# lazurite_rev3_2.net
KiCad netlist of a schematic drawn in EAGLE
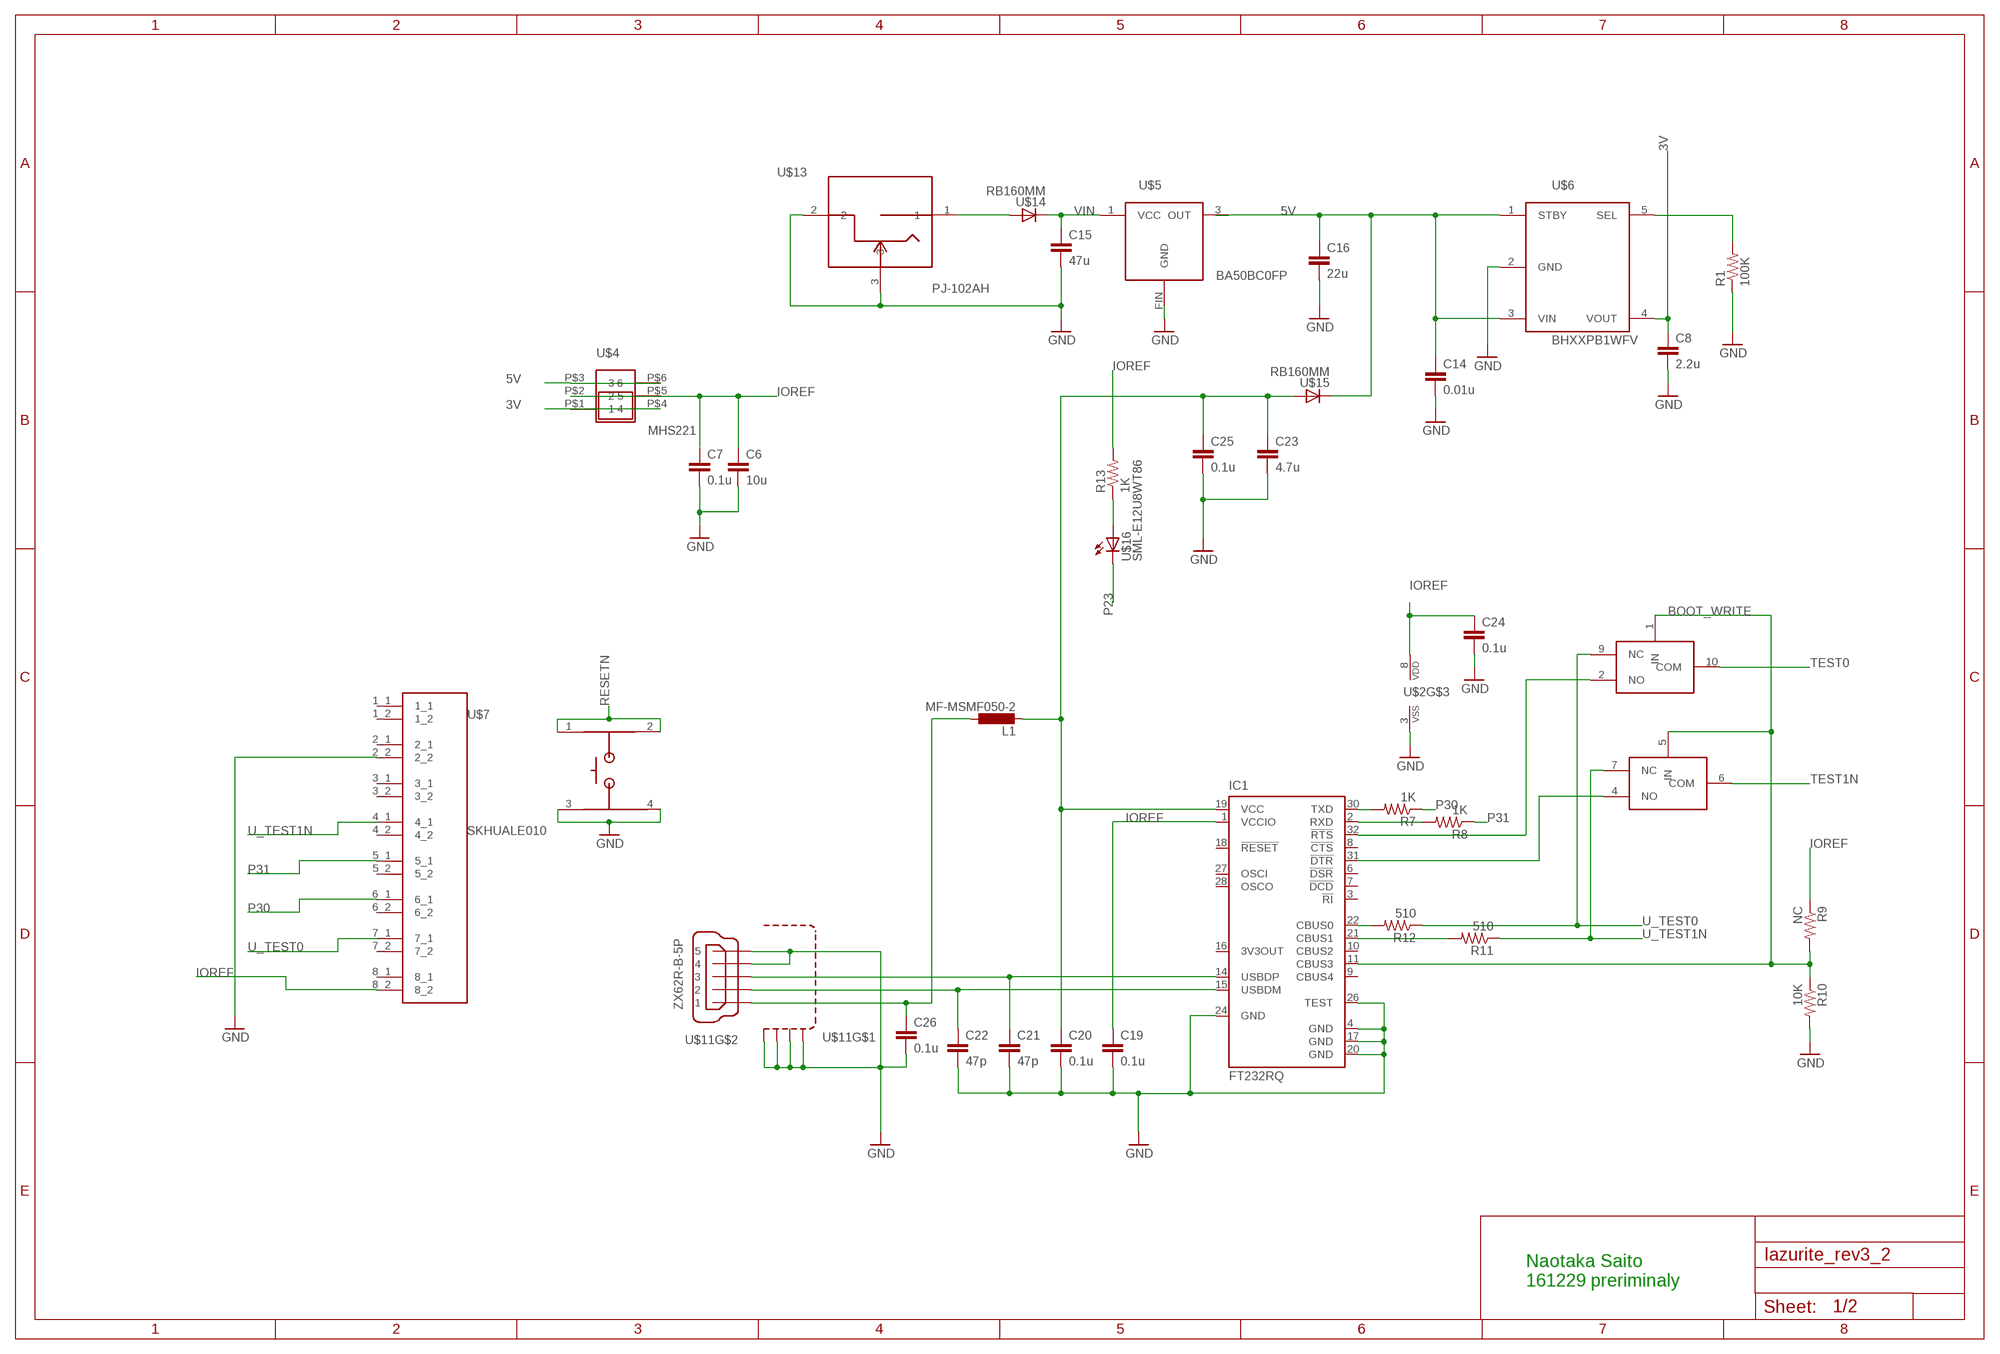
[diagram p0: schematic, sheet 1]
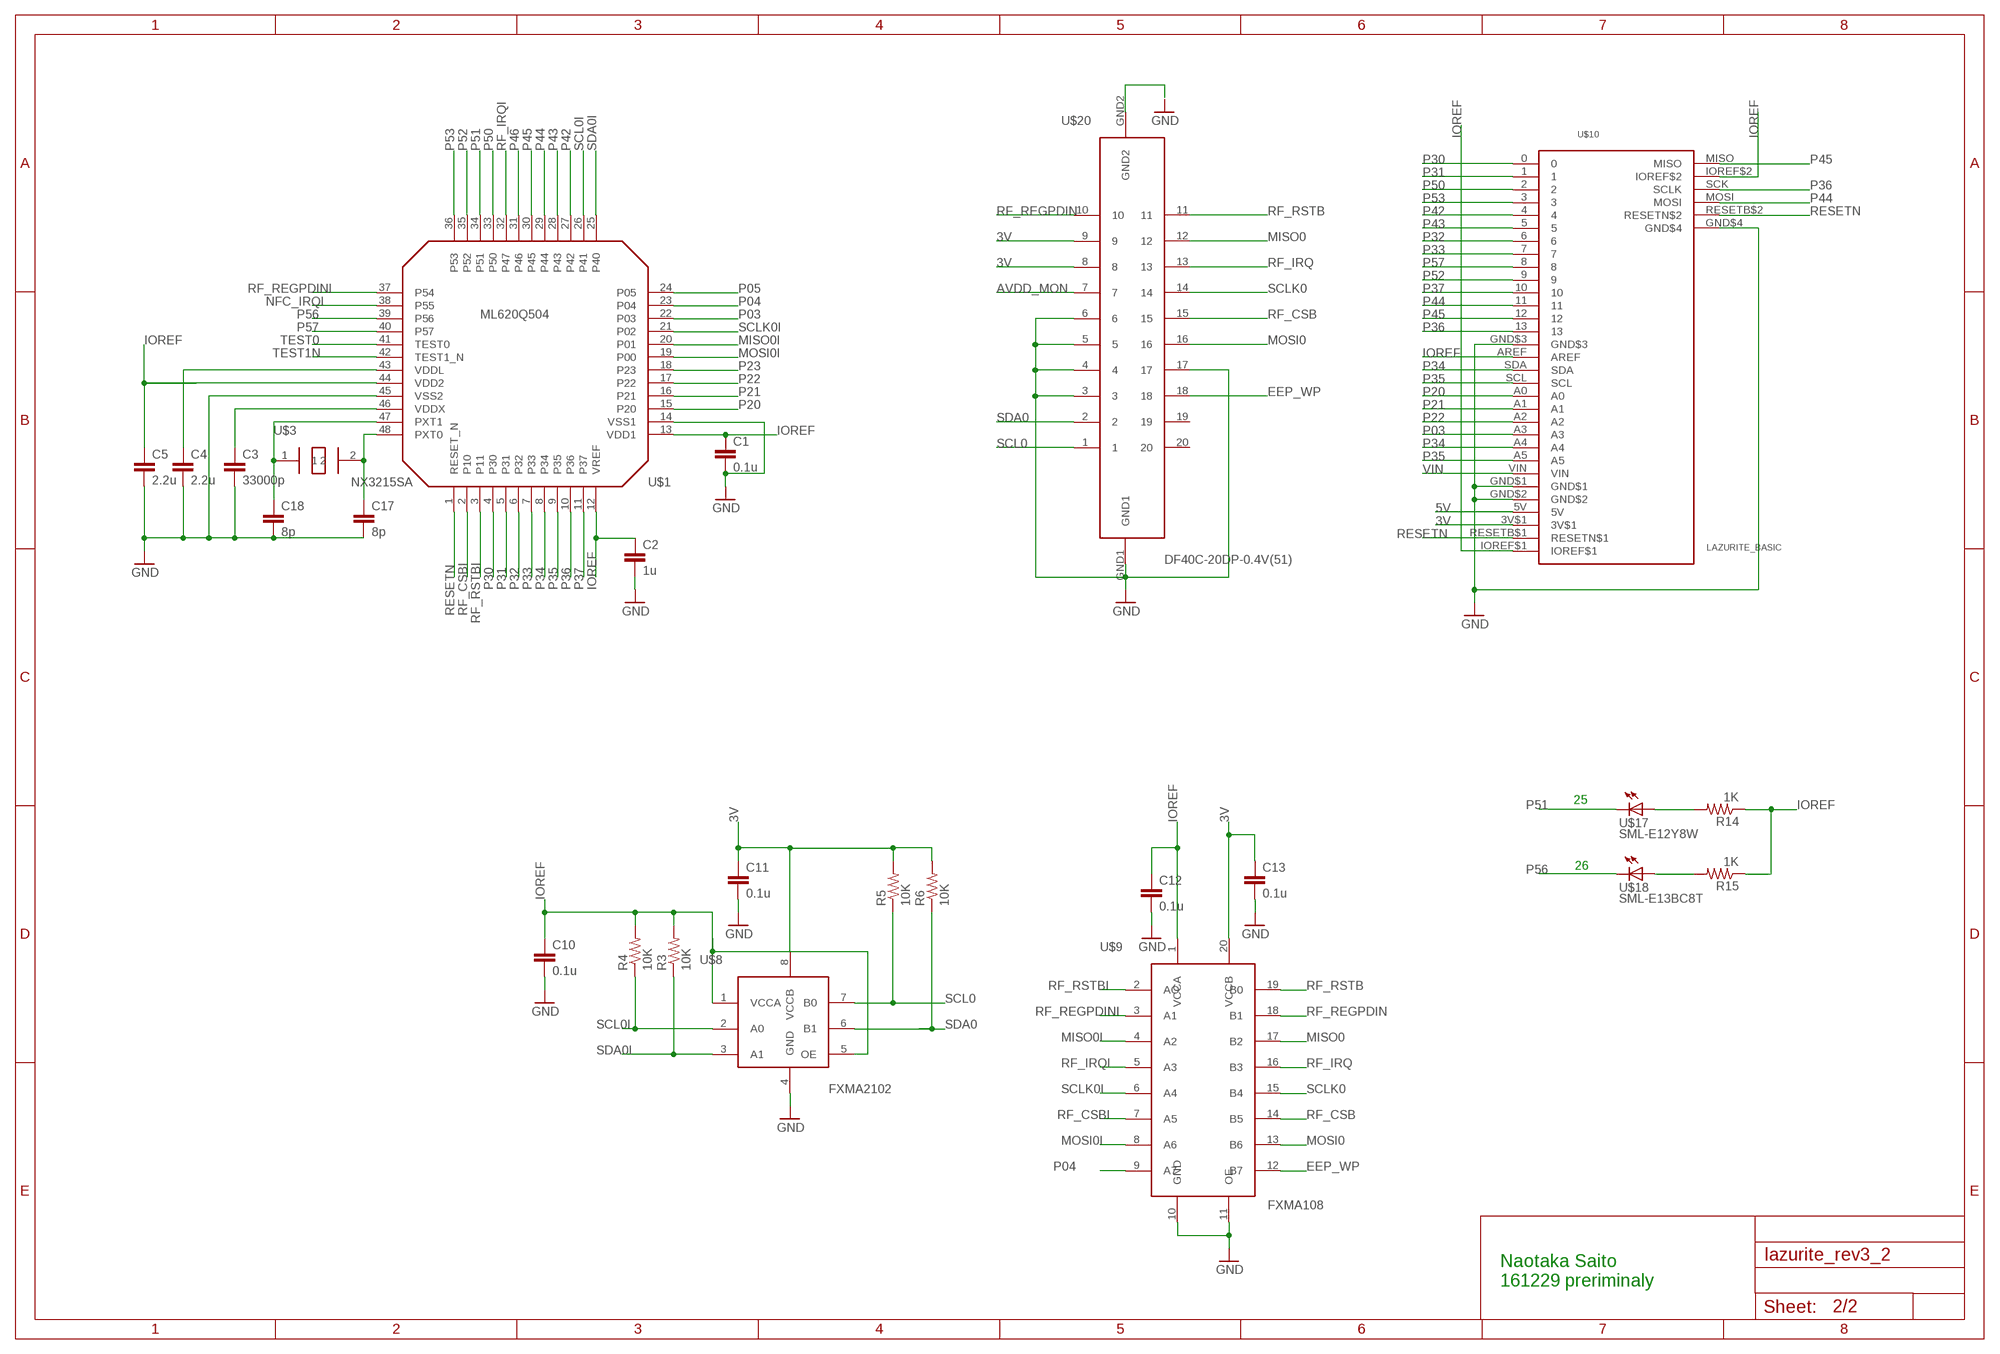
[diagram p1: schematic, sheet 2]

(export (version "E")
  (design (tool "Eeschema 10.0.6"))
  (components
    (comp (ref "C1")
      (value "0.1u")
      (footprint "eagle-import:C0402")
      (libsource (lib "eagle-import") (part "C-EUC0402"))
    )
    (comp (ref "C2")
      (value "1u")
      (footprint "eagle-import:C0402")
      (libsource (lib "eagle-import") (part "C-EUC0402"))
    )
    (comp (ref "C3")
      (value "33000p")
      (footprint "eagle-import:C0402")
      (libsource (lib "eagle-import") (part "C-EUC0402"))
    )
    (comp (ref "C4")
      (value "2.2u")
      (footprint "eagle-import:C0402")
      (libsource (lib "eagle-import") (part "C-EUC0402"))
    )
    (comp (ref "C5")
      (value "2.2u")
      (footprint "eagle-import:C0402")
      (libsource (lib "eagle-import") (part "C-EUC0402"))
    )
    (comp (ref "C10")
      (value "0.1u")
      (footprint "eagle-import:C0402")
      (libsource (lib "eagle-import") (part "C-EUC0402"))
    )
    (comp (ref "C11")
      (value "0.1u")
      (footprint "eagle-import:C0402")
      (libsource (lib "eagle-import") (part "C-EUC0402"))
    )
    (comp (ref "C12")
      (value "0.1u")
      (footprint "eagle-import:C0402")
      (libsource (lib "eagle-import") (part "C-EUC0402"))
    )
    (comp (ref "C13")
      (value "0.1u")
      (footprint "eagle-import:C0402")
      (libsource (lib "eagle-import") (part "C-EUC0402"))
    )
    (comp (ref "C17")
      (value "8p")
      (footprint "eagle-import:C0402")
      (libsource (lib "eagle-import") (part "C-EUC0402"))
    )
    (comp (ref "C18")
      (value "8p")
      (footprint "eagle-import:C0402")
      (libsource (lib "eagle-import") (part "C-EUC0402"))
    )
    (comp (ref "R3")
      (value "10K")
      (footprint "eagle-import:R0402")
      (libsource (lib "eagle-import") (part "R-US_R0402"))
    )
    (comp (ref "R4")
      (value "10K")
      (footprint "eagle-import:R0402")
      (libsource (lib "eagle-import") (part "R-US_R0402"))
    )
    (comp (ref "R5")
      (value "10K")
      (footprint "eagle-import:R0402")
      (libsource (lib "eagle-import") (part "R-US_R0402"))
    )
    (comp (ref "R6")
      (value "10K")
      (footprint "eagle-import:R0402")
      (libsource (lib "eagle-import") (part "R-US_R0402"))
    )
    (comp (ref "R14")
      (value "1K")
      (footprint "eagle-import:R0402")
      (libsource (lib "eagle-import") (part "R-US_R0402"))
    )
    (comp (ref "R15")
      (value "1K")
      (footprint "eagle-import:R0402")
      (libsource (lib "eagle-import") (part "R-US_R0402"))
    )
    (comp (ref "U$1")
      (value "ML620Q504")
      (footprint "eagle-import:ML620Q504")
      (libsource (lib "eagle-import") (part "ML620Q504"))
    )
    (comp (ref "U$3")
      (value "NX3215SA")
      (footprint "eagle-import:NX3215SA-32,768K-SFD-MUA-14")
      (libsource (lib "eagle-import") (part "NX3215SA"))
    )
    (comp (ref "U$8")
      (value "FXMA2102")
      (footprint "eagle-import:MICROPACK")
      (libsource (lib "eagle-import") (part "FXMA2102"))
    )
    (comp (ref "U$9")
      (value "FXMA108")
      (footprint "eagle-import:FXMA108")
      (libsource (lib "eagle-import") (part "FXMA108"))
    )
    (comp (ref "U$10")
      (value "LAZURITE_BASIC")
      (footprint "eagle-import:LAZURITE_BASIC")
      (libsource (lib "eagle-import") (part "LAZURITE_BASIC"))
    )
    (comp (ref "U$17")
      (value "SML-E12Y8W")
      (footprint "eagle-import:SML-E1X")
      (libsource (lib "eagle-import") (part "SML-E1X"))
    )
    (comp (ref "U$18")
      (value "SML-E13BC8T")
      (footprint "eagle-import:SML-E1X")
      (libsource (lib "eagle-import") (part "SML-E1X"))
    )
    (comp (ref "U$20")
      (value "DF40C-20DP-0.4V(51)")
      (footprint "eagle-import:BP3596A")
      (libsource (lib "eagle-import") (part "BP3596A"))
    )
    (comp (ref "C6")
      (value "10u")
      (footprint "eagle-import:C0402")
      (libsource (lib "eagle-import") (part "C-EUC0402"))
    )
    (comp (ref "C7")
      (value "0.1u")
      (footprint "eagle-import:C0402")
      (libsource (lib "eagle-import") (part "C-EUC0402"))
    )
    (comp (ref "C8")
      (value "2.2u")
      (footprint "eagle-import:C0402")
      (libsource (lib "eagle-import") (part "C-EUC0402"))
    )
    (comp (ref "C14")
      (value "0.01u")
      (footprint "eagle-import:C0402")
      (libsource (lib "eagle-import") (part "C-EUC0402"))
    )
    (comp (ref "C15")
      (value "47u")
      (footprint "eagle-import:C1210")
      (libsource (lib "eagle-import") (part "C-EUC1210"))
    )
    (comp (ref "C16")
      (value "22u")
      (footprint "eagle-import:C1206")
      (libsource (lib "eagle-import") (part "C-EUC1206"))
    )
    (comp (ref "C19")
      (value "0.1u")
      (footprint "eagle-import:C0402")
      (libsource (lib "eagle-import") (part "C-EUC0402"))
    )
    (comp (ref "C20")
      (value "0.1u")
      (footprint "eagle-import:C0402")
      (libsource (lib "eagle-import") (part "C-EUC0402"))
    )
    (comp (ref "C21")
      (value "47p")
      (footprint "eagle-import:C0402")
      (libsource (lib "eagle-import") (part "C-EUC0402"))
    )
    (comp (ref "C22")
      (value "47p")
      (footprint "eagle-import:C0402")
      (libsource (lib "eagle-import") (part "C-EUC0402"))
    )
    (comp (ref "C23")
      (value "4.7u")
      (footprint "eagle-import:C0402")
      (libsource (lib "eagle-import") (part "C-EUC0402"))
    )
    (comp (ref "C24")
      (value "0.1u")
      (footprint "eagle-import:C0402")
      (libsource (lib "eagle-import") (part "C-EUC0402"))
    )
    (comp (ref "C25")
      (value "0.1u")
      (footprint "eagle-import:C0402")
      (libsource (lib "eagle-import") (part "C-EUC0402"))
    )
    (comp (ref "C26")
      (value "0.1u")
      (footprint "eagle-import:C0402")
      (libsource (lib "eagle-import") (part "C-EUC0402"))
    )
    (comp (ref "IC1")
      (value "FT232RQ")
      (footprint "eagle-import:QFN32")
      (libsource (lib "eagle-import") (part "FT232RQ"))
    )
    (comp (ref "L1")
      (value "MF-MSMF050-2")
      (footprint "eagle-import:L1812")
      (libsource (lib "eagle-import") (part "L-EUL1812"))
    )
    (comp (ref "R1")
      (value "100K")
      (footprint "eagle-import:R0402")
      (libsource (lib "eagle-import") (part "R-US_R0402"))
    )
    (comp (ref "R7")
      (value "1K")
      (footprint "eagle-import:R0402")
      (libsource (lib "eagle-import") (part "R-US_R0402"))
    )
    (comp (ref "R8")
      (value "1K")
      (footprint "eagle-import:R0402")
      (libsource (lib "eagle-import") (part "R-US_R0402"))
    )
    (comp (ref "R9")
      (value "NC")
      (footprint "eagle-import:R0402")
      (libsource (lib "eagle-import") (part "R-US_R0402"))
    )
    (comp (ref "R10")
      (value "10K")
      (footprint "eagle-import:R0402")
      (libsource (lib "eagle-import") (part "R-US_R0402"))
    )
    (comp (ref "R11")
      (value "510")
      (footprint "eagle-import:R0402")
      (libsource (lib "eagle-import") (part "R-US_R0402"))
    )
    (comp (ref "R12")
      (value "510")
      (footprint "eagle-import:R0402")
      (libsource (lib "eagle-import") (part "R-US_R0402"))
    )
    (comp (ref "R13")
      (value "1K")
      (footprint "eagle-import:R0402")
      (libsource (lib "eagle-import") (part "R-US_R0402"))
    )
    (comp (ref "U$2")
      (value "TI-TS5A23159")
      (footprint "eagle-import:UQFN10")
      (libsource (lib "eagle-import") (part "TI-TS5A23159"))
    )
    (comp (ref "U$4")
      (value "MHS221")
      (footprint "eagle-import:MHS221")
      (libsource (lib "eagle-import") (part "MHS221"))
    )
    (comp (ref "U$5")
      (value "BA50BC0FP")
      (footprint "eagle-import:TO252-3")
      (libsource (lib "eagle-import") (part "BA50BC0FP"))
    )
    (comp (ref "U$6")
      (value "BHXXPB1WFV")
      (footprint "eagle-import:HVSOF5")
      (libsource (lib "eagle-import") (part "BHXXPB1WFV"))
    )
    (comp (ref "U$7")
      (value "SKHUALE010")
      (footprint "eagle-import:SKHUALE010")
      (libsource (lib "eagle-import") (part "SKHUALE010"))
    )
    (comp (ref "U$11")
      (value "ZX62R-B-5P")
      (footprint "eagle-import:ZX62R-B-5P")
      (libsource (lib "eagle-import") (part "MICRO-USB-SHIELD-ZX62R-B-5P"))
    )
    (comp (ref "U$12")
      (value "XB-1-X")
      (footprint "eagle-import:XB-1-X")
      (libsource (lib "eagle-import") (part "XB-1-X"))
    )
    (comp (ref "U$13")
      (value "PJ-102AH")
      (footprint "eagle-import:PJ-102H")
      (libsource (lib "eagle-import") (part "PJ-102AH"))
    )
    (comp (ref "U$14")
      (value "RB160MM")
      (footprint "eagle-import:RB160MM-30")
      (libsource (lib "eagle-import") (part "RB160MM"))
    )
    (comp (ref "U$15")
      (value "RB160MM")
      (footprint "eagle-import:RB160MM-30")
      (libsource (lib "eagle-import") (part "RB160MM"))
    )
    (comp (ref "U$16")
      (value "SML-E12U8WT86")
      (footprint "eagle-import:SML-E1X")
      (libsource (lib "eagle-import") (part "SML-E1X"))
    )
  )
  (nets
    (net (code "1") (name "3V") (class "Default")
      (node (ref "C11") (pin "1") (pinfunction "1_1") (pintype "passive"))
      (node (ref "C13") (pin "1") (pinfunction "1_1") (pintype "passive"))
      (node (ref "C8") (pin "1") (pinfunction "1_1") (pintype "passive"))
      (node (ref "R5") (pin "2") (pinfunction "2_2") (pintype "passive"))
      (node (ref "R6") (pin "2") (pinfunction "2_2") (pintype "passive"))
      (node (ref "U$10") (pin "3V$1") (pinfunction "3V$1_3V$1") (pintype "power_in"))
      (node (ref "U$20") (pin "8") (pinfunction "8_8") (pintype "bidirectional"))
      (node (ref "U$20") (pin "9") (pinfunction "9_9") (pintype "bidirectional"))
      (node (ref "U$4") (pin "P$1") (pinfunction "1_P$1") (pintype "bidirectional"))
      (node (ref "U$4") (pin "P$4") (pinfunction "4_P$4") (pintype "bidirectional"))
      (node (ref "U$6") (pin "4") (pinfunction "VOUT_4") (pintype "bidirectional"))
      (node (ref "U$8") (pin "8") (pinfunction "VCCB_8") (pintype "bidirectional"))
      (node (ref "U$9") (pin "20") (pinfunction "VCCB_20") (pintype "bidirectional"))
    )
    (net (code "2") (name "5V") (class "Default")
      (node (ref "C14") (pin "1") (pinfunction "1_1") (pintype "passive"))
      (node (ref "C16") (pin "1") (pinfunction "1_1") (pintype "passive"))
      (node (ref "U$10") (pin "5V") (pinfunction "5V_5V") (pintype "power_in"))
      (node (ref "U$15") (pin "C") (pinfunction "C_C") (pintype "passive"))
      (node (ref "U$4") (pin "P$3") (pinfunction "3_P$3") (pintype "bidirectional"))
      (node (ref "U$4") (pin "P$6") (pinfunction "6_P$6") (pintype "bidirectional"))
      (node (ref "U$5") (pin "3") (pinfunction "OUT_3") (pintype "bidirectional"))
      (node (ref "U$6") (pin "1") (pinfunction "STBY_1") (pintype "bidirectional"))
      (node (ref "U$6") (pin "3") (pinfunction "VIN_3") (pintype "bidirectional"))
    )
    (net (code "3") (name "AVDD_MON") (class "Default")
      (node (ref "U$20") (pin "7") (pinfunction "7_7") (pintype "bidirectional"))
    )
    (net (code "4") (name "BOOT_WRITE") (class "Default")
      (node (ref "IC1") (pin "11") (pinfunction "CBUS3_11") (pintype "bidirectional"))
      (node (ref "R10") (pin "1") (pinfunction "1_1") (pintype "passive"))
      (node (ref "R9") (pin "2") (pinfunction "2_2") (pintype "passive"))
      (node (ref "U$2") (pin "1") (pinfunction "IN_1") (pintype "bidirectional"))
      (node (ref "U$2") (pin "5") (pinfunction "IN_5") (pintype "bidirectional"))
    )
    (net (code "5") (name "EEP_WP") (class "Default")
      (node (ref "U$20") (pin "18") (pinfunction "18_18") (pintype "bidirectional"))
      (node (ref "U$9") (pin "12") (pinfunction "B7_12") (pintype "bidirectional"))
    )
    (net (code "6") (name "GND") (class "Default")
      (node (ref "C1") (pin "2") (pinfunction "2_2") (pintype "passive"))
      (node (ref "C10") (pin "2") (pinfunction "2_2") (pintype "passive"))
      (node (ref "C11") (pin "2") (pinfunction "2_2") (pintype "passive"))
      (node (ref "C12") (pin "2") (pinfunction "2_2") (pintype "passive"))
      (node (ref "C13") (pin "2") (pinfunction "2_2") (pintype "passive"))
      (node (ref "C14") (pin "2") (pinfunction "2_2") (pintype "passive"))
      (node (ref "C15") (pin "2") (pinfunction "2_2") (pintype "passive"))
      (node (ref "C16") (pin "2") (pinfunction "2_2") (pintype "passive"))
      (node (ref "C17") (pin "2") (pinfunction "2_2") (pintype "passive"))
      (node (ref "C18") (pin "2") (pinfunction "2_2") (pintype "passive"))
      (node (ref "C19") (pin "2") (pinfunction "2_2") (pintype "passive"))
      (node (ref "C2") (pin "2") (pinfunction "2_2") (pintype "passive"))
      (node (ref "C20") (pin "2") (pinfunction "2_2") (pintype "passive"))
      (node (ref "C21") (pin "2") (pinfunction "2_2") (pintype "passive"))
      (node (ref "C22") (pin "2") (pinfunction "2_2") (pintype "passive"))
      (node (ref "C23") (pin "2") (pinfunction "2_2") (pintype "passive"))
      (node (ref "C24") (pin "2") (pinfunction "2_2") (pintype "passive"))
      (node (ref "C25") (pin "2") (pinfunction "2_2") (pintype "passive"))
      (node (ref "C26") (pin "2") (pinfunction "2_2") (pintype "passive"))
      (node (ref "C3") (pin "2") (pinfunction "2_2") (pintype "passive"))
      (node (ref "C4") (pin "2") (pinfunction "2_2") (pintype "passive"))
      (node (ref "C5") (pin "2") (pinfunction "2_2") (pintype "passive"))
      (node (ref "C6") (pin "2") (pinfunction "2_2") (pintype "passive"))
      (node (ref "C7") (pin "2") (pinfunction "2_2") (pintype "passive"))
      (node (ref "C8") (pin "2") (pinfunction "2_2") (pintype "passive"))
      (node (ref "IC1") (pin "17") (pinfunction "GND_17") (pintype "power_in"))
      (node (ref "IC1") (pin "20") (pinfunction "GND_20") (pintype "power_in"))
      (node (ref "IC1") (pin "24") (pinfunction "GND_24") (pintype "power_in"))
      (node (ref "IC1") (pin "26") (pinfunction "TEST_26") (pintype "input"))
      (node (ref "IC1") (pin "4") (pinfunction "GND_4") (pintype "power_in"))
      (node (ref "R1") (pin "1") (pinfunction "1_1") (pintype "passive"))
      (node (ref "R10") (pin "2") (pinfunction "2_2") (pintype "passive"))
      (node (ref "U$1") (pin "14") (pinfunction "VSS1_14") (pintype "bidirectional"))
      (node (ref "U$1") (pin "45") (pinfunction "VSS2_45") (pintype "bidirectional"))
      (node (ref "U$10") (pin "GND$1") (pinfunction "GND$1_GND$1") (pintype "power_in"))
      (node (ref "U$10") (pin "GND$2") (pinfunction "GND$2_GND$2") (pintype "power_in"))
      (node (ref "U$10") (pin "GND$3") (pinfunction "GND$3_GND$3") (pintype "power_in"))
      (node (ref "U$10") (pin "GND$4") (pinfunction "GND$4_GND$4") (pintype "power_in"))
      (node (ref "U$11") (pin "4") (pinfunction "4_4") (pintype "input"))
      (node (ref "U$11") (pin "5") (pinfunction "5_5") (pintype "input"))
      (node (ref "U$11") (pin "M1") (pinfunction "S1_M1") (pintype "passive"))
      (node (ref "U$11") (pin "M2") (pinfunction "S2_M2") (pintype "passive"))
      (node (ref "U$11") (pin "M3") (pinfunction "S3_M3") (pintype "passive"))
      (node (ref "U$11") (pin "M4") (pinfunction "S4_M4") (pintype "passive"))
      (node (ref "U$12") (pin "2_2") (pinfunction "2_2_2_2") (pintype "bidirectional"))
      (node (ref "U$13") (pin "2") (pinfunction "2_2") (pintype "bidirectional"))
      (node (ref "U$13") (pin "3") (pinfunction "3_3") (pintype "bidirectional"))
      (node (ref "U$2") (pin "3") (pinfunction "VSS_3") (pintype "power_in"))
      (node (ref "U$20") (pin "17") (pinfunction "17_17") (pintype "bidirectional"))
      (node (ref "U$20") (pin "3") (pinfunction "3_3") (pintype "bidirectional"))
      (node (ref "U$20") (pin "4") (pinfunction "4_4") (pintype "bidirectional"))
      (node (ref "U$20") (pin "5") (pinfunction "5_5") (pintype "bidirectional"))
      (node (ref "U$20") (pin "6") (pinfunction "6_6") (pintype "bidirectional"))
      (node (ref "U$20") (pin "GND1") (pinfunction "GND1_GND1") (pintype "bidirectional"))
      (node (ref "U$5") (pin "FIN") (pinfunction "GND_FIN") (pintype "bidirectional"))
      (node (ref "U$6") (pin "2") (pinfunction "GND_2") (pintype "bidirectional"))
      (node (ref "U$7") (pin "3") (pinfunction "3_3") (pintype "bidirectional"))
      (node (ref "U$7") (pin "4") (pinfunction "4_4") (pintype "bidirectional"))
      (node (ref "U$8") (pin "4") (pinfunction "GND_4") (pintype "bidirectional"))
      (node (ref "U$9") (pin "10") (pinfunction "GND_10") (pintype "bidirectional"))
      (node (ref "U$9") (pin "11") (pinfunction "OE_11") (pintype "bidirectional"))
    )
    (net (code "7") (name "IOREF") (class "Default")
      (node (ref "C1") (pin "1") (pinfunction "1_1") (pintype "passive"))
      (node (ref "C10") (pin "1") (pinfunction "1_1") (pintype "passive"))
      (node (ref "C12") (pin "1") (pinfunction "1_1") (pintype "passive"))
      (node (ref "C19") (pin "1") (pinfunction "1_1") (pintype "passive"))
      (node (ref "C2") (pin "1") (pinfunction "1_1") (pintype "passive"))
      (node (ref "C24") (pin "1") (pinfunction "1_1") (pintype "passive"))
      (node (ref "C5") (pin "1") (pinfunction "1_1") (pintype "passive"))
      (node (ref "C6") (pin "1") (pinfunction "1_1") (pintype "passive"))
      (node (ref "C7") (pin "1") (pinfunction "1_1") (pintype "passive"))
      (node (ref "IC1") (pin "1") (pinfunction "VCCIO_1") (pintype "power_in"))
      (node (ref "R13") (pin "2") (pinfunction "2_2") (pintype "passive"))
      (node (ref "R14") (pin "1") (pinfunction "1_1") (pintype "passive"))
      (node (ref "R15") (pin "1") (pinfunction "1_1") (pintype "passive"))
      (node (ref "R3") (pin "2") (pinfunction "2_2") (pintype "passive"))
      (node (ref "R4") (pin "2") (pinfunction "2_2") (pintype "passive"))
      (node (ref "R9") (pin "1") (pinfunction "1_1") (pintype "passive"))
      (node (ref "U$1") (pin "12") (pinfunction "VREF_12") (pintype "bidirectional"))
      (node (ref "U$1") (pin "13") (pinfunction "VDD1_13") (pintype "bidirectional"))
      (node (ref "U$1") (pin "44") (pinfunction "VDD2_44") (pintype "bidirectional"))
      (node (ref "U$10") (pin "AREF") (pinfunction "AREF_AREF") (pintype "power_in"))
      (node (ref "U$10") (pin "IOREF$1") (pinfunction "IOREF$1_IOREF$1") (pintype "bidirectional"))
      (node (ref "U$10") (pin "IOREF$2") (pinfunction "IOREF$2_IOREF$2") (pintype "power_in"))
      (node (ref "U$12") (pin "8_2") (pinfunction "8_2_8_2") (pintype "bidirectional"))
      (node (ref "U$2") (pin "8") (pinfunction "VDD_8") (pintype "power_in"))
      (node (ref "U$4") (pin "P$2") (pinfunction "2_P$2") (pintype "bidirectional"))
      (node (ref "U$4") (pin "P$5") (pinfunction "5_P$5") (pintype "bidirectional"))
      (node (ref "U$8") (pin "1") (pinfunction "VCCA_1") (pintype "bidirectional"))
      (node (ref "U$8") (pin "5") (pinfunction "OE_5") (pintype "bidirectional"))
      (node (ref "U$9") (pin "1") (pinfunction "VCCA_1") (pintype "bidirectional"))
    )
    (net (code "8") (name "MISO0") (class "Default")
      (node (ref "U$20") (pin "12") (pinfunction "12_12") (pintype "bidirectional"))
      (node (ref "U$9") (pin "17") (pinfunction "B2_17") (pintype "bidirectional"))
    )
    (net (code "9") (name "MISO0I") (class "Default")
      (node (ref "U$1") (pin "20") (pinfunction "P01_20") (pintype "bidirectional"))
      (node (ref "U$9") (pin "4") (pinfunction "A2_4") (pintype "bidirectional"))
    )
    (net (code "10") (name "MOSI0") (class "Default")
      (node (ref "U$20") (pin "16") (pinfunction "16_16") (pintype "bidirectional"))
      (node (ref "U$9") (pin "13") (pinfunction "B6_13") (pintype "bidirectional"))
    )
    (net (code "11") (name "MOSI0I") (class "Default")
      (node (ref "U$1") (pin "19") (pinfunction "P00_19") (pintype "bidirectional"))
      (node (ref "U$9") (pin "8") (pinfunction "A6_8") (pintype "bidirectional"))
    )
    (net (code "12") (name "NFC_IRQI") (class "Default")
      (node (ref "U$1") (pin "38") (pinfunction "P55_38") (pintype "bidirectional"))
    )
    (net (code "13") (name "Net-(C26-Pad1)") (class "Default")
      (node (ref "C26") (pin "1") (pinfunction "1_1") (pintype "passive"))
      (node (ref "L1") (pin "1") (pinfunction "1_1") (pintype "passive"))
      (node (ref "U$11") (pin "1") (pinfunction "1_1") (pintype "input"))
    )
    (net (code "14") (name "Net-(IC1-CBUS0)") (class "Default")
      (node (ref "IC1") (pin "22") (pinfunction "CBUS0_22") (pintype "bidirectional"))
      (node (ref "R12") (pin "2") (pinfunction "2_2") (pintype "passive"))
    )
    (net (code "15") (name "Net-(IC1-CBUS1)") (class "Default")
      (node (ref "IC1") (pin "21") (pinfunction "CBUS1_21") (pintype "bidirectional"))
      (node (ref "R11") (pin "2") (pinfunction "2_2") (pintype "passive"))
    )
    (net (code "16") (name "Net-(IC1-RXD)") (class "Default")
      (node (ref "IC1") (pin "2") (pinfunction "RXD_2") (pintype "input"))
      (node (ref "R8") (pin "2") (pinfunction "2_2") (pintype "passive"))
    )
    (net (code "17") (name "Net-(IC1-TXD)") (class "Default")
      (node (ref "IC1") (pin "30") (pinfunction "TXD_30") (pintype "output"))
      (node (ref "R7") (pin "2") (pinfunction "2_2") (pintype "passive"))
    )
    (net (code "18") (name "Net-(IC1-USBDM)") (class "Default")
      (node (ref "C22") (pin "1") (pinfunction "1_1") (pintype "passive"))
      (node (ref "IC1") (pin "15") (pinfunction "USBDM_15") (pintype "bidirectional"))
      (node (ref "U$11") (pin "2") (pinfunction "2_2") (pintype "input"))
    )
    (net (code "19") (name "Net-(IC1-USBDP)") (class "Default")
      (node (ref "C21") (pin "1") (pinfunction "1_1") (pintype "passive"))
      (node (ref "IC1") (pin "14") (pinfunction "USBDP_14") (pintype "bidirectional"))
      (node (ref "U$11") (pin "3") (pinfunction "3_3") (pintype "input"))
    )
    (net (code "20") (name "Net-(IC1-VCC)") (class "Default")
      (node (ref "C20") (pin "1") (pinfunction "1_1") (pintype "passive"))
      (node (ref "C23") (pin "1") (pinfunction "1_1") (pintype "passive"))
      (node (ref "C25") (pin "1") (pinfunction "1_1") (pintype "passive"))
      (node (ref "IC1") (pin "19") (pinfunction "VCC_19") (pintype "power_in"))
      (node (ref "L1") (pin "2") (pinfunction "2_2") (pintype "passive"))
      (node (ref "U$15") (pin "A") (pinfunction "A_A") (pintype "passive"))
    )
    (net (code "21") (name "Net-(IC1-~{DTR})") (class "Default")
      (node (ref "IC1") (pin "31") (pinfunction "~{DTR}_31") (pintype "output"))
      (node (ref "U$2") (pin "4") (pinfunction "NO_4") (pintype "bidirectional"))
    )
    (net (code "22") (name "Net-(IC1-~{RTS})") (class "Default")
      (node (ref "IC1") (pin "32") (pinfunction "~{RTS}_32") (pintype "output"))
      (node (ref "U$2") (pin "2") (pinfunction "NO_2") (pintype "bidirectional"))
    )
    (net (code "23") (name "Net-(R13-Pad1)") (class "Default")
      (node (ref "R13") (pin "1") (pinfunction "1_1") (pintype "passive"))
      (node (ref "U$16") (pin "A") (pinfunction "A_A") (pintype "passive"))
    )
    (net (code "24") (name "Net-(R14-Pad2)") (class "Default")
      (node (ref "R14") (pin "2") (pinfunction "2_2") (pintype "passive"))
      (node (ref "U$17") (pin "A") (pinfunction "A_A") (pintype "passive"))
    )
    (net (code "25") (name "Net-(R15-Pad2)") (class "Default")
      (node (ref "R15") (pin "2") (pinfunction "2_2") (pintype "passive"))
      (node (ref "U$18") (pin "A") (pinfunction "A_A") (pintype "passive"))
    )
    (net (code "26") (name "Net-(U$1-PXT0)") (class "Default")
      (node (ref "C17") (pin "1") (pinfunction "1_1") (pintype "passive"))
      (node (ref "U$1") (pin "48") (pinfunction "PXT0_48") (pintype "bidirectional"))
      (node (ref "U$3") (pin "2") (pinfunction "2_2") (pintype "bidirectional"))
    )
    (net (code "27") (name "Net-(U$1-PXT1)") (class "Default")
      (node (ref "C18") (pin "1") (pinfunction "1_1") (pintype "passive"))
      (node (ref "U$1") (pin "47") (pinfunction "PXT1_47") (pintype "bidirectional"))
      (node (ref "U$3") (pin "1") (pinfunction "1_1") (pintype "bidirectional"))
    )
    (net (code "28") (name "Net-(U$1-VDDL)") (class "Default")
      (node (ref "C4") (pin "1") (pinfunction "1_1") (pintype "passive"))
      (node (ref "U$1") (pin "43") (pinfunction "VDDL_43") (pintype "bidirectional"))
    )
    (net (code "29") (name "Net-(U$1-VDDX)") (class "Default")
      (node (ref "C3") (pin "1") (pinfunction "1_1") (pintype "passive"))
      (node (ref "U$1") (pin "46") (pinfunction "VDDX_46") (pintype "bidirectional"))
    )
    (net (code "30") (name "Net-(U$6-SEL)") (class "Default")
      (node (ref "R1") (pin "2") (pinfunction "2_2") (pintype "passive"))
      (node (ref "U$6") (pin "5") (pinfunction "SEL_5") (pintype "bidirectional"))
    )
    (net (code "31") (name "Net-(U$13-Pad1)") (class "Default")
      (node (ref "U$13") (pin "1") (pinfunction "1_1") (pintype "bidirectional"))
      (node (ref "U$14") (pin "A") (pinfunction "A_A") (pintype "passive"))
    )
    (net (code "32") (name "P03") (class "Default")
      (node (ref "U$1") (pin "22") (pinfunction "P03_22") (pintype "bidirectional"))
      (node (ref "U$10") (pin "A3") (pinfunction "A3_A3") (pintype "bidirectional"))
    )
    (net (code "33") (name "P04") (class "Default")
      (node (ref "U$1") (pin "23") (pinfunction "P04_23") (pintype "bidirectional"))
      (node (ref "U$9") (pin "9") (pinfunction "A7_9") (pintype "bidirectional"))
    )
    (net (code "34") (name "P05") (class "Default")
      (node (ref "U$1") (pin "24") (pinfunction "P05_24") (pintype "bidirectional"))
    )
    (net (code "35") (name "P20") (class "Default")
      (node (ref "U$1") (pin "15") (pinfunction "P20_15") (pintype "bidirectional"))
      (node (ref "U$10") (pin "A0") (pinfunction "A0_A0") (pintype "bidirectional"))
    )
    (net (code "36") (name "P21") (class "Default")
      (node (ref "U$1") (pin "16") (pinfunction "P21_16") (pintype "bidirectional"))
      (node (ref "U$10") (pin "A1") (pinfunction "A1_A1") (pintype "bidirectional"))
    )
    (net (code "37") (name "P22") (class "Default")
      (node (ref "U$1") (pin "17") (pinfunction "P22_17") (pintype "bidirectional"))
      (node (ref "U$10") (pin "A2") (pinfunction "A2_A2") (pintype "bidirectional"))
    )
    (net (code "38") (name "P23") (class "Default")
      (node (ref "U$1") (pin "18") (pinfunction "P23_18") (pintype "bidirectional"))
      (node (ref "U$16") (pin "C") (pinfunction "C_C") (pintype "passive"))
    )
    (net (code "39") (name "P30") (class "Default")
      (node (ref "R7") (pin "1") (pinfunction "1_1") (pintype "passive"))
      (node (ref "U$1") (pin "4") (pinfunction "P30_4") (pintype "bidirectional"))
      (node (ref "U$10") (pin "0") (pinfunction "0_0") (pintype "bidirectional"))
      (node (ref "U$12") (pin "6_1") (pinfunction "6_1_6_1") (pintype "bidirectional"))
    )
    (net (code "40") (name "P31") (class "Default")
      (node (ref "R8") (pin "1") (pinfunction "1_1") (pintype "passive"))
      (node (ref "U$1") (pin "5") (pinfunction "P31_5") (pintype "bidirectional"))
      (node (ref "U$10") (pin "1") (pinfunction "1_1") (pintype "bidirectional"))
      (node (ref "U$12") (pin "5_1") (pinfunction "5_1_5_1") (pintype "bidirectional"))
    )
    (net (code "41") (name "P32") (class "Default")
      (node (ref "U$1") (pin "6") (pinfunction "P32_6") (pintype "bidirectional"))
      (node (ref "U$10") (pin "6") (pinfunction "6_6") (pintype "bidirectional"))
    )
    (net (code "42") (name "P33") (class "Default")
      (node (ref "U$1") (pin "7") (pinfunction "P33_7") (pintype "bidirectional"))
      (node (ref "U$10") (pin "7") (pinfunction "7_7") (pintype "bidirectional"))
    )
    (net (code "43") (name "P34") (class "Default")
      (node (ref "U$1") (pin "8") (pinfunction "P34_8") (pintype "bidirectional"))
      (node (ref "U$10") (pin "A4") (pinfunction "A4_A4") (pintype "bidirectional"))
      (node (ref "U$10") (pin "SDA") (pinfunction "SDA_SDA") (pintype "bidirectional"))
    )
    (net (code "44") (name "P35") (class "Default")
      (node (ref "U$1") (pin "9") (pinfunction "P35_9") (pintype "bidirectional"))
      (node (ref "U$10") (pin "A5") (pinfunction "A5_A5") (pintype "bidirectional"))
      (node (ref "U$10") (pin "SCL") (pinfunction "SCL_SCL") (pintype "bidirectional"))
    )
    (net (code "45") (name "P36") (class "Default")
      (node (ref "U$1") (pin "10") (pinfunction "P36_10") (pintype "bidirectional"))
      (node (ref "U$10") (pin "13") (pinfunction "13_13") (pintype "bidirectional"))
      (node (ref "U$10") (pin "SCK") (pinfunction "SCLK_SCK") (pintype "bidirectional"))
    )
    (net (code "46") (name "P37") (class "Default")
      (node (ref "U$1") (pin "11") (pinfunction "P37_11") (pintype "bidirectional"))
      (node (ref "U$10") (pin "10") (pinfunction "10_10") (pintype "bidirectional"))
    )
    (net (code "47") (name "P42") (class "Default")
      (node (ref "U$1") (pin "27") (pinfunction "P42_27") (pintype "bidirectional"))
      (node (ref "U$10") (pin "4") (pinfunction "4_4") (pintype "bidirectional"))
    )
    (net (code "48") (name "P43") (class "Default")
      (node (ref "U$1") (pin "28") (pinfunction "P43_28") (pintype "bidirectional"))
      (node (ref "U$10") (pin "5") (pinfunction "5_5") (pintype "bidirectional"))
    )
    (net (code "49") (name "P44") (class "Default")
      (node (ref "U$1") (pin "29") (pinfunction "P44_29") (pintype "bidirectional"))
      (node (ref "U$10") (pin "11") (pinfunction "11_11") (pintype "bidirectional"))
      (node (ref "U$10") (pin "MOSI") (pinfunction "MOSI_MOSI") (pintype "bidirectional"))
    )
    (net (code "50") (name "P45") (class "Default")
      (node (ref "U$1") (pin "30") (pinfunction "P45_30") (pintype "bidirectional"))
      (node (ref "U$10") (pin "12") (pinfunction "12_12") (pintype "bidirectional"))
      (node (ref "U$10") (pin "MISO") (pinfunction "MISO_MISO") (pintype "bidirectional"))
    )
    (net (code "51") (name "P46") (class "Default")
      (node (ref "U$1") (pin "31") (pinfunction "P46_31") (pintype "bidirectional"))
    )
    (net (code "52") (name "P50") (class "Default")
      (node (ref "U$1") (pin "33") (pinfunction "P50_33") (pintype "bidirectional"))
      (node (ref "U$10") (pin "2") (pinfunction "2_2") (pintype "bidirectional"))
    )
    (net (code "53") (name "P51") (class "Default")
      (node (ref "U$1") (pin "34") (pinfunction "P51_34") (pintype "bidirectional"))
      (node (ref "U$17") (pin "C") (pinfunction "C_C") (pintype "passive"))
    )
    (net (code "54") (name "P52") (class "Default")
      (node (ref "U$1") (pin "35") (pinfunction "P52_35") (pintype "bidirectional"))
      (node (ref "U$10") (pin "9") (pinfunction "9_9") (pintype "bidirectional"))
    )
    (net (code "55") (name "P53") (class "Default")
      (node (ref "U$1") (pin "36") (pinfunction "P53_36") (pintype "bidirectional"))
      (node (ref "U$10") (pin "3") (pinfunction "3_3") (pintype "bidirectional"))
    )
    (net (code "56") (name "P56") (class "Default")
      (node (ref "U$1") (pin "39") (pinfunction "P56_39") (pintype "bidirectional"))
      (node (ref "U$18") (pin "C") (pinfunction "C_C") (pintype "passive"))
    )
    (net (code "57") (name "P57") (class "Default")
      (node (ref "U$1") (pin "40") (pinfunction "P57_40") (pintype "bidirectional"))
      (node (ref "U$10") (pin "8") (pinfunction "8_8") (pintype "bidirectional"))
    )
    (net (code "58") (name "RESETN") (class "Default")
      (node (ref "U$1") (pin "1") (pinfunction "RESET_N_1") (pintype "bidirectional"))
      (node (ref "U$10") (pin "RESETB$1") (pinfunction "RESETN$1_RESETB$1") (pintype "bidirectional"))
      (node (ref "U$10") (pin "RESETB$2") (pinfunction "RESETN$2_RESETB$2") (pintype "bidirectional"))
      (node (ref "U$7") (pin "1") (pinfunction "1_1") (pintype "bidirectional"))
      (node (ref "U$7") (pin "2") (pinfunction "2_2") (pintype "bidirectional"))
    )
    (net (code "59") (name "RF_CSB") (class "Default")
      (node (ref "U$20") (pin "15") (pinfunction "15_15") (pintype "bidirectional"))
      (node (ref "U$9") (pin "14") (pinfunction "B5_14") (pintype "bidirectional"))
    )
    (net (code "60") (name "RF_CSBI") (class "Default")
      (node (ref "U$1") (pin "2") (pinfunction "P10_2") (pintype "bidirectional"))
      (node (ref "U$9") (pin "7") (pinfunction "A5_7") (pintype "bidirectional"))
    )
    (net (code "61") (name "RF_IRQ") (class "Default")
      (node (ref "U$20") (pin "13") (pinfunction "13_13") (pintype "bidirectional"))
      (node (ref "U$9") (pin "16") (pinfunction "B3_16") (pintype "bidirectional"))
    )
    (net (code "62") (name "RF_IRQI") (class "Default")
      (node (ref "U$1") (pin "32") (pinfunction "P47_32") (pintype "bidirectional"))
      (node (ref "U$9") (pin "5") (pinfunction "A3_5") (pintype "bidirectional"))
    )
    (net (code "63") (name "RF_REGPDIN") (class "Default")
      (node (ref "U$20") (pin "10") (pinfunction "10_10") (pintype "bidirectional"))
      (node (ref "U$9") (pin "18") (pinfunction "B1_18") (pintype "bidirectional"))
    )
    (net (code "64") (name "RF_REGPDINI") (class "Default")
      (node (ref "U$1") (pin "37") (pinfunction "P54_37") (pintype "bidirectional"))
      (node (ref "U$9") (pin "3") (pinfunction "A1_3") (pintype "bidirectional"))
    )
    (net (code "65") (name "RF_RSTB") (class "Default")
      (node (ref "U$20") (pin "11") (pinfunction "11_11") (pintype "bidirectional"))
      (node (ref "U$9") (pin "19") (pinfunction "B0_19") (pintype "bidirectional"))
    )
    (net (code "66") (name "RF_RSTBI") (class "Default")
      (node (ref "U$1") (pin "3") (pinfunction "P11_3") (pintype "bidirectional"))
      (node (ref "U$9") (pin "2") (pinfunction "AO_2") (pintype "bidirectional"))
    )
    (net (code "67") (name "SCL0") (class "Default")
      (node (ref "R5") (pin "1") (pinfunction "1_1") (pintype "passive"))
      (node (ref "U$20") (pin "1") (pinfunction "1_1") (pintype "bidirectional"))
      (node (ref "U$8") (pin "7") (pinfunction "B0_7") (pintype "bidirectional"))
    )
    (net (code "68") (name "SCL0I") (class "Default")
      (node (ref "R4") (pin "1") (pinfunction "1_1") (pintype "passive"))
      (node (ref "U$1") (pin "26") (pinfunction "P41_26") (pintype "bidirectional"))
      (node (ref "U$8") (pin "2") (pinfunction "A0_2") (pintype "bidirectional"))
    )
    (net (code "69") (name "SCLK0") (class "Default")
      (node (ref "U$20") (pin "14") (pinfunction "14_14") (pintype "bidirectional"))
      (node (ref "U$9") (pin "15") (pinfunction "B4_15") (pintype "bidirectional"))
    )
    (net (code "70") (name "SCLK0I") (class "Default")
      (node (ref "U$1") (pin "21") (pinfunction "P02_21") (pintype "bidirectional"))
      (node (ref "U$9") (pin "6") (pinfunction "A4_6") (pintype "bidirectional"))
    )
    (net (code "71") (name "SDA0") (class "Default")
      (node (ref "R6") (pin "1") (pinfunction "1_1") (pintype "passive"))
      (node (ref "U$20") (pin "2") (pinfunction "2_2") (pintype "bidirectional"))
      (node (ref "U$8") (pin "6") (pinfunction "B1_6") (pintype "bidirectional"))
    )
    (net (code "72") (name "SDA0I") (class "Default")
      (node (ref "R3") (pin "1") (pinfunction "1_1") (pintype "passive"))
      (node (ref "U$1") (pin "25") (pinfunction "P40_25") (pintype "bidirectional"))
      (node (ref "U$8") (pin "3") (pinfunction "A1_3") (pintype "bidirectional"))
    )
    (net (code "73") (name "TEST0") (class "Default")
      (node (ref "U$1") (pin "41") (pinfunction "TEST0_41") (pintype "bidirectional"))
      (node (ref "U$2") (pin "10") (pinfunction "COM_10") (pintype "bidirectional"))
    )
    (net (code "74") (name "TEST1N") (class "Default")
      (node (ref "U$1") (pin "42") (pinfunction "TEST1_N_42") (pintype "bidirectional"))
      (node (ref "U$2") (pin "6") (pinfunction "COM_6") (pintype "bidirectional"))
    )
    (net (code "75") (name "U_TEST0") (class "Default")
      (node (ref "R12") (pin "1") (pinfunction "1_1") (pintype "passive"))
      (node (ref "U$12") (pin "7_1") (pinfunction "7_1_7_1") (pintype "bidirectional"))
      (node (ref "U$2") (pin "9") (pinfunction "NC_9") (pintype "bidirectional"))
    )
    (net (code "76") (name "U_TEST1N") (class "Default")
      (node (ref "R11") (pin "1") (pinfunction "1_1") (pintype "passive"))
      (node (ref "U$12") (pin "4_1") (pinfunction "4_1_4_1") (pintype "bidirectional"))
      (node (ref "U$2") (pin "7") (pinfunction "NC_7") (pintype "bidirectional"))
    )
    (net (code "77") (name "VIN") (class "Default")
      (node (ref "C15") (pin "1") (pinfunction "1_1") (pintype "passive"))
      (node (ref "U$10") (pin "VIN") (pinfunction "VIN_VIN") (pintype "power_in"))
      (node (ref "U$14") (pin "C") (pinfunction "C_C") (pintype "passive"))
      (node (ref "U$5") (pin "1") (pinfunction "VCC_1") (pintype "bidirectional"))
    )
    (net (code "78") (name "unconnected-(IC1-3V3OUT-Pad16)") (class "Default")
      (node (ref "IC1") (pin "16") (pinfunction "3V3OUT_16") (pintype "output"))
    )
    (net (code "79") (name "unconnected-(IC1-CBUS2-Pad10)") (class "Default")
      (node (ref "IC1") (pin "10") (pinfunction "CBUS2_10") (pintype "bidirectional"))
    )
    (net (code "80") (name "unconnected-(IC1-CBUS4-Pad9)") (class "Default")
      (node (ref "IC1") (pin "9") (pinfunction "CBUS4_9") (pintype "bidirectional"))
    )
    (net (code "81") (name "unconnected-(IC1-OSCI-Pad27)") (class "Default")
      (node (ref "IC1") (pin "27") (pinfunction "OSCI_27") (pintype "input"))
    )
    (net (code "82") (name "unconnected-(IC1-OSCO-Pad28)") (class "Default")
      (node (ref "IC1") (pin "28") (pinfunction "OSCO_28") (pintype "output"))
    )
    (net (code "83") (name "unconnected-(IC1-~{CTS}-Pad8)") (class "Default")
      (node (ref "IC1") (pin "8") (pinfunction "~{CTS}_8") (pintype "input"))
    )
    (net (code "84") (name "unconnected-(IC1-~{DCD}-Pad7)") (class "Default")
      (node (ref "IC1") (pin "7") (pinfunction "~{DCD}_7") (pintype "input"))
    )
    (net (code "85") (name "unconnected-(IC1-~{DSR}-Pad6)") (class "Default")
      (node (ref "IC1") (pin "6") (pinfunction "~{DSR}_6") (pintype "input"))
    )
    (net (code "86") (name "unconnected-(IC1-~{RESET}-Pad18)") (class "Default")
      (node (ref "IC1") (pin "18") (pinfunction "~{RESET}_18") (pintype "input"))
    )
    (net (code "87") (name "unconnected-(IC1-~{RI}-Pad3)") (class "Default")
      (node (ref "IC1") (pin "3") (pinfunction "~{RI}_3") (pintype "input"))
    )
    (net (code "88") (name "unconnected-(U$12-Pad1_1)") (class "Default")
      (node (ref "U$12") (pin "1_1") (pinfunction "1_1_1_1") (pintype "bidirectional"))
    )
    (net (code "89") (name "unconnected-(U$12-Pad1_2)") (class "Default")
      (node (ref "U$12") (pin "1_2") (pinfunction "1_2_1_2") (pintype "bidirectional"))
    )
    (net (code "90") (name "unconnected-(U$12-Pad2_1)") (class "Default")
      (node (ref "U$12") (pin "2_1") (pinfunction "2_1_2_1") (pintype "bidirectional"))
    )
    (net (code "91") (name "unconnected-(U$12-Pad3_1)") (class "Default")
      (node (ref "U$12") (pin "3_1") (pinfunction "3_1_3_1") (pintype "bidirectional"))
    )
    (net (code "92") (name "unconnected-(U$12-Pad3_2)") (class "Default")
      (node (ref "U$12") (pin "3_2") (pinfunction "3_2_3_2") (pintype "bidirectional"))
    )
    (net (code "93") (name "unconnected-(U$12-Pad4_2)") (class "Default")
      (node (ref "U$12") (pin "4_2") (pinfunction "4_2_4_2") (pintype "bidirectional"))
    )
    (net (code "94") (name "unconnected-(U$12-Pad5_2)") (class "Default")
      (node (ref "U$12") (pin "5_2") (pinfunction "5_2_5_2") (pintype "bidirectional"))
    )
    (net (code "95") (name "unconnected-(U$12-Pad6_2)") (class "Default")
      (node (ref "U$12") (pin "6_2") (pinfunction "6_2_6_2") (pintype "bidirectional"))
    )
    (net (code "96") (name "unconnected-(U$12-Pad7_2)") (class "Default")
      (node (ref "U$12") (pin "7_2") (pinfunction "7_2_7_2") (pintype "bidirectional"))
    )
    (net (code "97") (name "unconnected-(U$12-Pad8_1)") (class "Default")
      (node (ref "U$12") (pin "8_1") (pinfunction "8_1_8_1") (pintype "bidirectional"))
    )
    (net (code "98") (name "unconnected-(U$20-Pad19)") (class "Default")
      (node (ref "U$20") (pin "19") (pinfunction "19_19") (pintype "bidirectional"))
    )
    (net (code "99") (name "unconnected-(U$20-Pad20)") (class "Default")
      (node (ref "U$20") (pin "20") (pinfunction "20_20") (pintype "bidirectional"))
    )
    (net (code "100") (name "unconnected-(U$20-PadGND2)") (class "Default")
      (node (ref "U$20") (pin "GND2") (pinfunction "GND2_GND2") (pintype "bidirectional"))
    )
  )
)
